# MR_UartConnector.net
KiCad netlist of a schematic drawn in Altium Designer
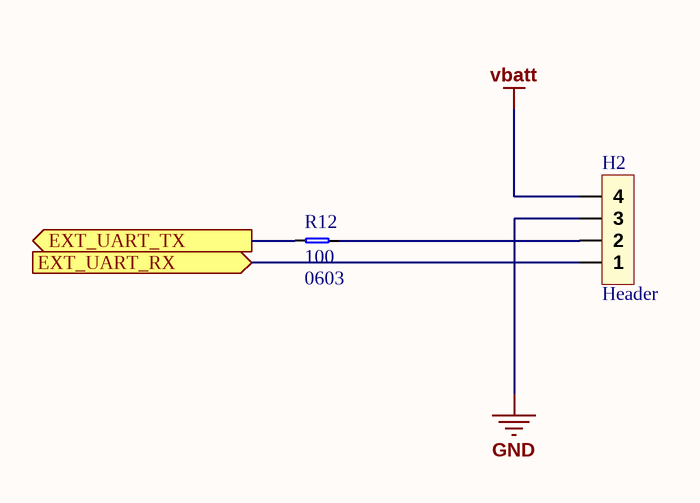
[diagram p0: MR_UartConnector.SchDoc]

(export (version "E")
  (design (tool "Eeschema 10.0.6"))
  (components
    (comp (ref "H2")
      (value "Header")
      (footprint "HE14 1x4 Straight")
      (description "Header 4x1 PIns")
      (libsource (lib "MiniRobot") (part "Header_4x1"))
    )
    (comp (ref "R12")
      (value "100")
      (footprint "0603_RES_LD")
      (description "Resistor")
      (fields (field (name "PACKAGE") "0603"))
      (libsource (lib "MiniRobot") (part "Resistor"))
    )
  )
  (nets
    (net (code "1") (name "/EXT_UART_RX") (class "Default")
      (node (ref "H2") (pin "1") (pinfunction "1_1") (pintype "passive"))
    )
    (net (code "2") (name "/EXT_UART_TX") (class "Default")
      (node (ref "R12") (pin "1") (pinfunction "1_1") (pintype "passive"))
    )
    (net (code "3") (name "GND") (class "Default")
      (node (ref "H2") (pin "3") (pinfunction "3_3") (pintype "passive"))
    )
    (net (code "4") (name "Net-(H2-Pad2)") (class "Default")
      (node (ref "H2") (pin "2") (pinfunction "2_2") (pintype "passive"))
      (node (ref "R12") (pin "2") (pinfunction "2_2") (pintype "passive"))
    )
    (net (code "5") (name "vbatt") (class "Default")
      (node (ref "H2") (pin "4") (pinfunction "4_4") (pintype "passive"))
    )
  )
)
